# Schutz.net
KiCad netlist of a schematic drawn in EAGLE
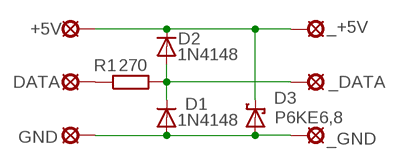
[diagram p0: schematic, sheet 1]

(export (version "E")
  (design (tool "Eeschema 10.0.6"))
  (components
    (comp (ref "+5V")
      (value "LSP11")
      (footprint "eagle-import:LSP11")
      (libsource (lib "eagle-import") (part "LSP11"))
    )
    (comp (ref "D1")
      (value "1N4148")
      (footprint "eagle-import:DO35-7")
      (libsource (lib "eagle-import") (part "1N4148DO35-7"))
    )
    (comp (ref "D2")
      (value "1N4148")
      (footprint "eagle-import:DO35-7")
      (libsource (lib "eagle-import") (part "1N4148DO35-7"))
    )
    (comp (ref "D3")
      (value "P6KE6,8")
      (footprint "eagle-import:CB417-15")
      (libsource (lib "eagle-import") (part "P6KEXX"))
    )
    (comp (ref "DATA")
      (value "LSP11")
      (footprint "eagle-import:LSP11")
      (libsource (lib "eagle-import") (part "LSP11"))
    )
    (comp (ref "GND")
      (value "LSP11")
      (footprint "eagle-import:LSP11")
      (libsource (lib "eagle-import") (part "LSP11"))
    )
    (comp (ref "R1")
      (value "270")
      (footprint "eagle-import:0207_7")
      (libsource (lib "eagle-import") (part "R-EU_0207/7"))
    )
    (comp (ref "_+5V")
      (value "LSP11")
      (footprint "eagle-import:LSP11")
      (libsource (lib "eagle-import") (part "LSP11"))
    )
    (comp (ref "_DATA")
      (value "LSP11")
      (footprint "eagle-import:LSP11")
      (libsource (lib "eagle-import") (part "LSP11"))
    )
    (comp (ref "_GND")
      (value "LSP11")
      (footprint "eagle-import:LSP11")
      (libsource (lib "eagle-import") (part "LSP11"))
    )
  )
  (nets
    (net (code "1") (name "Net-(+5V-PadMP)") (class "Default")
      (node (ref "+5V") (pin "MP") (pinfunction "MP_MP") (pintype "passive"))
      (node (ref "D2") (pin "C") (pinfunction "C_C") (pintype "passive"))
      (node (ref "D3") (pin "C") (pinfunction "C_C") (pintype "passive"))
      (node (ref "_+5V") (pin "MP") (pinfunction "MP_MP") (pintype "passive"))
    )
    (net (code "2") (name "Net-(D1-PadA)") (class "Default")
      (node (ref "D1") (pin "A") (pinfunction "A_A") (pintype "passive"))
      (node (ref "D3") (pin "A") (pinfunction "A_A") (pintype "passive"))
      (node (ref "GND") (pin "MP") (pinfunction "MP_MP") (pintype "passive"))
      (node (ref "_GND") (pin "MP") (pinfunction "MP_MP") (pintype "passive"))
    )
    (net (code "3") (name "Net-(D1-PadC)") (class "Default")
      (node (ref "D1") (pin "C") (pinfunction "C_C") (pintype "passive"))
      (node (ref "D2") (pin "A") (pinfunction "A_A") (pintype "passive"))
      (node (ref "R1") (pin "2") (pinfunction "2_2") (pintype "passive"))
      (node (ref "_DATA") (pin "MP") (pinfunction "MP_MP") (pintype "passive"))
    )
    (net (code "4") (name "Net-(DATA-PadMP)") (class "Default")
      (node (ref "DATA") (pin "MP") (pinfunction "MP_MP") (pintype "passive"))
      (node (ref "R1") (pin "1") (pinfunction "1_1") (pintype "passive"))
    )
  )
)
